# compare2_2.net
KiCad netlist of a schematic drawn in EAGLE
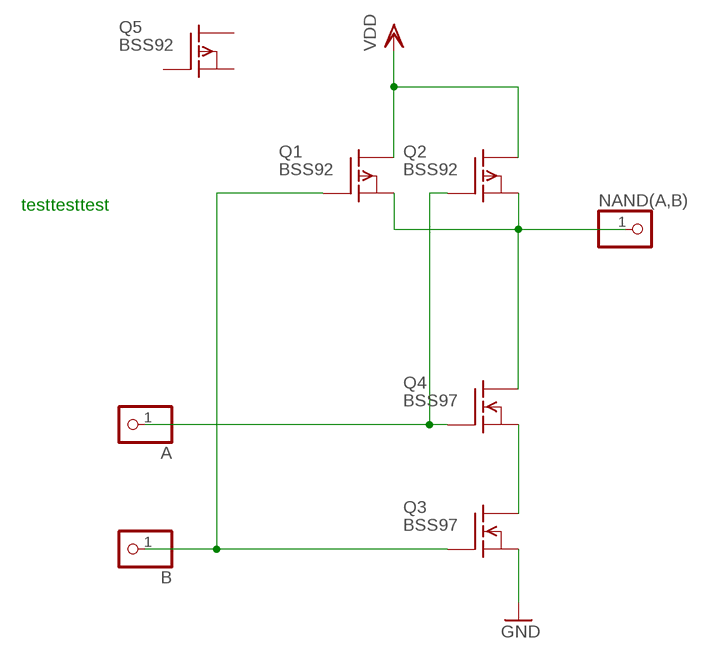
[diagram p0: schematic, sheet 1]

(export (version "E")
  (design (tool "Eeschema 10.0.6"))
  (components
    (comp (ref "A")
      (value "PINHD-1X1")
      (footprint "eagle-import:1X01")
      (libsource (lib "eagle-import") (part "PINHD-1X1"))
    )
    (comp (ref "B")
      (value "PINHD-1X1")
      (footprint "eagle-import:1X01")
      (libsource (lib "eagle-import") (part "PINHD-1X1"))
    )
    (comp (ref "NAND(A,B)")
      (value "PINHD-1X1")
      (footprint "eagle-import:1X01")
      (libsource (lib "eagle-import") (part "PINHD-1X1"))
    )
    (comp (ref "Q1")
      (value "BSS92")
      (footprint "eagle-import:TO92")
      (libsource (lib "eagle-import") (part "BSS92"))
    )
    (comp (ref "Q2")
      (value "BSS92")
      (footprint "eagle-import:TO92")
      (libsource (lib "eagle-import") (part "BSS92"))
    )
    (comp (ref "Q3")
      (value "BSS97")
      (footprint "eagle-import:TO202")
      (libsource (lib "eagle-import") (part "BSS97"))
    )
    (comp (ref "Q4")
      (value "BSS97")
      (footprint "eagle-import:TO202")
      (libsource (lib "eagle-import") (part "BSS97"))
    )
    (comp (ref "Q5")
      (value "BSS92")
      (footprint "eagle-import:TO92")
      (libsource (lib "eagle-import") (part "BSS92"))
    )
  )
  (nets
    (net (code "1") (name "GND") (class "Default")
      (node (ref "Q3") (pin "1") (pinfunction "S_1") (pintype "passive"))
    )
    (net (code "2") (name "Net-(Q1-G)") (class "Default")
      (node (ref "B") (pin "1") (pinfunction "1_1") (pintype "passive"))
      (node (ref "Q1") (pin "1") (pinfunction "G_1") (pintype "passive"))
      (node (ref "Q3") (pin "3") (pinfunction "G_3") (pintype "passive"))
    )
    (net (code "3") (name "Net-(Q1-S)") (class "Default")
      (node (ref "NAND(A,B)") (pin "1") (pinfunction "1_1") (pintype "passive"))
      (node (ref "Q1") (pin "3") (pinfunction "S_3") (pintype "passive"))
      (node (ref "Q2") (pin "3") (pinfunction "S_3") (pintype "passive"))
      (node (ref "Q4") (pin "2") (pinfunction "D_2") (pintype "passive"))
    )
    (net (code "4") (name "Net-(Q2-G)") (class "Default")
      (node (ref "A") (pin "1") (pinfunction "1_1") (pintype "passive"))
      (node (ref "Q2") (pin "1") (pinfunction "G_1") (pintype "passive"))
      (node (ref "Q4") (pin "3") (pinfunction "G_3") (pintype "passive"))
    )
    (net (code "5") (name "Net-(Q3-D)") (class "Default")
      (node (ref "Q3") (pin "2") (pinfunction "D_2") (pintype "passive"))
      (node (ref "Q4") (pin "1") (pinfunction "S_1") (pintype "passive"))
    )
    (net (code "6") (name "VDD") (class "Default")
      (node (ref "Q1") (pin "2") (pinfunction "D_2") (pintype "passive"))
      (node (ref "Q2") (pin "2") (pinfunction "D_2") (pintype "passive"))
    )
    (net (code "7") (name "unconnected-(Q5-D-Pad2)") (class "Default")
      (node (ref "Q5") (pin "2") (pinfunction "D_2") (pintype "passive"))
    )
    (net (code "8") (name "unconnected-(Q5-G-Pad1)") (class "Default")
      (node (ref "Q5") (pin "1") (pinfunction "G_1") (pintype "passive"))
    )
    (net (code "9") (name "unconnected-(Q5-S-Pad3)") (class "Default")
      (node (ref "Q5") (pin "3") (pinfunction "S_3") (pintype "passive"))
    )
  )
)
